# ADC108S022_PINOUT.net
KiCad netlist of a schematic drawn in Altium Designer
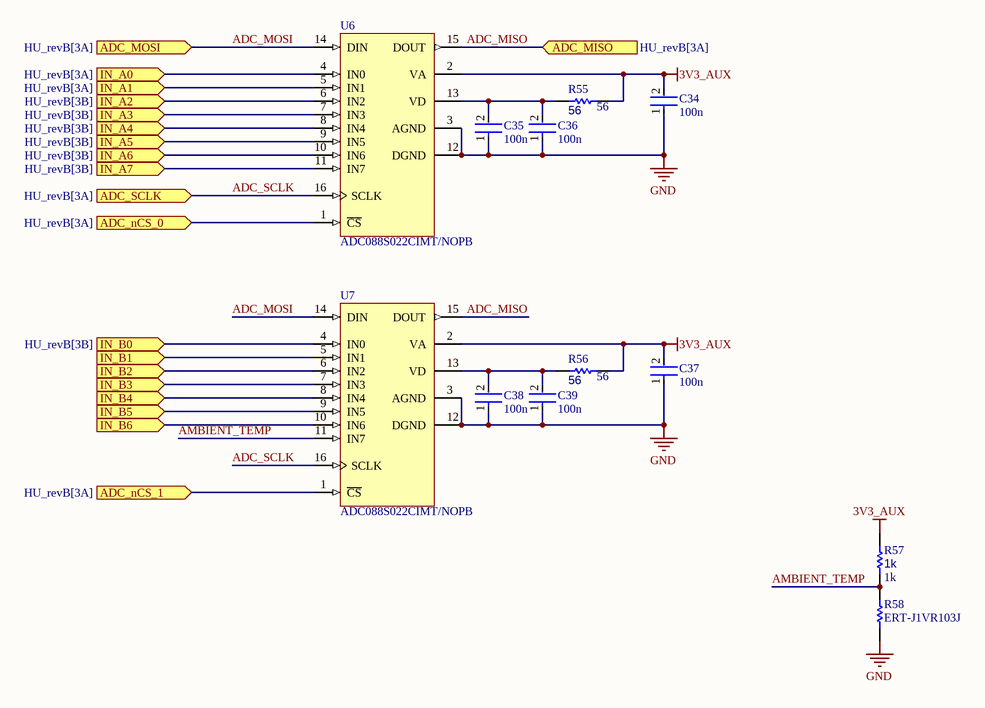
[diagram p0: ADC108S022_PINOUT.SchDoc]

(export (version "E")
  (design (tool "Eeschema 10.0.6"))
  (components
    (comp (ref "C34")
      (value "100n")
      (footprint "FP-0402-L_1_0_0_05-W_0_5-IPC_A")
      (description "LARGE PADS, 0402 CAP, CHANGE COMMENT TO MATCH REAL P/N")
      (libsource (lib "Space Concordia") (part "b4654b650e69147ec39a6b967a45e02"))
    )
    (comp (ref "C35")
      (value "100n")
      (footprint "FP-0402-L_1_0_0_05-W_0_5-IPC_A")
      (description "LARGE PADS, 0402 CAP, CHANGE COMMENT TO MATCH REAL P/N")
      (libsource (lib "Space Concordia") (part "b4654b650e69147ec39a6b967a45e02"))
    )
    (comp (ref "C36")
      (value "100n")
      (footprint "FP-0402-L_1_0_0_05-W_0_5-IPC_A")
      (description "LARGE PADS, 0402 CAP, CHANGE COMMENT TO MATCH REAL P/N")
      (libsource (lib "Space Concordia") (part "b4654b650e69147ec39a6b967a45e02"))
    )
    (comp (ref "C37")
      (value "100n")
      (footprint "FP-0402-L_1_0_0_05-W_0_5-IPC_A")
      (description "LARGE PADS, 0402 CAP, CHANGE COMMENT TO MATCH REAL P/N")
      (libsource (lib "Space Concordia") (part "b4654b650e69147ec39a6b967a45e02"))
    )
    (comp (ref "C38")
      (value "100n")
      (footprint "FP-0402-L_1_0_0_05-W_0_5-IPC_A")
      (description "LARGE PADS, 0402 CAP, CHANGE COMMENT TO MATCH REAL P/N")
      (libsource (lib "Space Concordia") (part "b4654b650e69147ec39a6b967a45e02"))
    )
    (comp (ref "C39")
      (value "100n")
      (footprint "FP-0402-L_1_0_0_05-W_0_5-IPC_A")
      (description "LARGE PADS, 0402 CAP, CHANGE COMMENT TO MATCH REAL P/N")
      (libsource (lib "Space Concordia") (part "b4654b650e69147ec39a6b967a45e02"))
    )
    (comp (ref "R55")
      (value "56")
      (footprint "R0603B")
      (description "Resistor")
      (fields (field (name "ALTIUM_VALUE") "56"))
      (libsource (lib "Space Concordia") (part "Resistor"))
    )
    (comp (ref "R56")
      (value "56")
      (footprint "R0603B")
      (description "Resistor")
      (fields (field (name "ALTIUM_VALUE") "56"))
      (libsource (lib "Space Concordia") (part "Resistor"))
    )
    (comp (ref "R57")
      (value "1k")
      (footprint "R0603B")
      (description "Resistor")
      (fields (field (name "ALTIUM_VALUE") "1k"))
      (libsource (lib "Space Concordia") (part "Resistor"))
    )
    (comp (ref "R58")
      (value "ERT-J1VR103J")
      (footprint "RESC1608X90X30ML15T20")
      (fields (field (name "MANUFACTURER") "Panasonic"))
      (libsource (lib "Altium Content Vault") (part "RES"))
    )
    (comp (ref "U6")
      (value "ADC088S022CIMT/NOPB")
      (footprint "MTC16_L")
      (description "8-Channel, 50 kSPS to 200 kSPS, 8-Bit A/D Converter, 16-pin TSSOP, Pb-Free")
      (fields (field (name "MANUFACTURER") "National Semiconductor"))
      (libsource (lib "Altium Content Vault") (part "CON-ADC-ADC108S052CIMT"))
    )
    (comp (ref "U7")
      (value "ADC088S022CIMT/NOPB")
      (footprint "MTC16_L")
      (description "8-Channel, 50 kSPS to 200 kSPS, 8-Bit A/D Converter, 16-pin TSSOP, Pb-Free")
      (fields (field (name "MANUFACTURER") "National Semiconductor"))
      (libsource (lib "Altium Content Vault") (part "CON-ADC-ADC108S052CIMT"))
    )
  )
  (nets
    (net (code "1") (name "/ADC_MISO") (class "Default")
      (node (ref "U6") (pin "15") (pinfunction "DOUT_15") (pintype "output"))
      (node (ref "U7") (pin "15") (pinfunction "DOUT_15") (pintype "output"))
    )
    (net (code "2") (name "/ADC_MOSI") (class "Default")
      (node (ref "U6") (pin "14") (pinfunction "DIN_14") (pintype "input"))
      (node (ref "U7") (pin "14") (pinfunction "DIN_14") (pintype "input"))
    )
    (net (code "3") (name "/ADC_SCLK") (class "Default")
      (node (ref "U6") (pin "16") (pinfunction "SCLK_16") (pintype "input"))
      (node (ref "U7") (pin "16") (pinfunction "SCLK_16") (pintype "input"))
    )
    (net (code "4") (name "/ADC_nCS_0") (class "Default")
      (node (ref "U6") (pin "1") (pinfunction "~{CS}_1") (pintype "input"))
    )
    (net (code "5") (name "/ADC_nCS_1") (class "Default")
      (node (ref "U7") (pin "1") (pinfunction "~{CS}_1") (pintype "input"))
    )
    (net (code "6") (name "/AMBIENT_TEMP") (class "Default")
      (node (ref "R57") (pin "2") (pinfunction "2_2") (pintype "passive"))
      (node (ref "R58") (pin "2") (pinfunction "2_2") (pintype "passive"))
      (node (ref "U7") (pin "11") (pinfunction "IN7_11") (pintype "input"))
    )
    (net (code "7") (name "/IN_A0") (class "Default")
      (node (ref "U6") (pin "4") (pinfunction "IN0_4") (pintype "input"))
    )
    (net (code "8") (name "/IN_A1") (class "Default")
      (node (ref "U6") (pin "5") (pinfunction "IN1_5") (pintype "input"))
    )
    (net (code "9") (name "/IN_A2") (class "Default")
      (node (ref "U6") (pin "6") (pinfunction "IN2_6") (pintype "input"))
    )
    (net (code "10") (name "/IN_A3") (class "Default")
      (node (ref "U6") (pin "7") (pinfunction "IN3_7") (pintype "input"))
    )
    (net (code "11") (name "/IN_A4") (class "Default")
      (node (ref "U6") (pin "8") (pinfunction "IN4_8") (pintype "input"))
    )
    (net (code "12") (name "/IN_A5") (class "Default")
      (node (ref "U6") (pin "9") (pinfunction "IN5_9") (pintype "input"))
    )
    (net (code "13") (name "/IN_A6") (class "Default")
      (node (ref "U6") (pin "10") (pinfunction "IN6_10") (pintype "input"))
    )
    (net (code "14") (name "/IN_A7") (class "Default")
      (node (ref "U6") (pin "11") (pinfunction "IN7_11") (pintype "input"))
    )
    (net (code "15") (name "/IN_B0") (class "Default")
      (node (ref "U7") (pin "4") (pinfunction "IN0_4") (pintype "input"))
    )
    (net (code "16") (name "/IN_B1") (class "Default")
      (node (ref "U7") (pin "5") (pinfunction "IN1_5") (pintype "input"))
    )
    (net (code "17") (name "/IN_B2") (class "Default")
      (node (ref "U7") (pin "6") (pinfunction "IN2_6") (pintype "input"))
    )
    (net (code "18") (name "/IN_B3") (class "Default")
      (node (ref "U7") (pin "7") (pinfunction "IN3_7") (pintype "input"))
    )
    (net (code "19") (name "/IN_B4") (class "Default")
      (node (ref "U7") (pin "8") (pinfunction "IN4_8") (pintype "input"))
    )
    (net (code "20") (name "/IN_B5") (class "Default")
      (node (ref "U7") (pin "9") (pinfunction "IN5_9") (pintype "input"))
    )
    (net (code "21") (name "/IN_B6") (class "Default")
      (node (ref "U7") (pin "10") (pinfunction "IN6_10") (pintype "input"))
    )
    (net (code "22") (name "3V3_AUX") (class "Default")
      (node (ref "C34") (pin "2") (pinfunction "2_2") (pintype "passive"))
      (node (ref "C37") (pin "2") (pinfunction "2_2") (pintype "passive"))
      (node (ref "R55") (pin "1") (pinfunction "1_1") (pintype "passive"))
      (node (ref "R56") (pin "1") (pinfunction "1_1") (pintype "passive"))
      (node (ref "R57") (pin "1") (pinfunction "1_1") (pintype "passive"))
      (node (ref "U6") (pin "2") (pinfunction "VA_2") (pintype "power_in"))
      (node (ref "U7") (pin "2") (pinfunction "VA_2") (pintype "power_in"))
    )
    (net (code "23") (name "GND") (class "Default")
      (node (ref "C34") (pin "1") (pinfunction "1_1") (pintype "passive"))
      (node (ref "C35") (pin "1") (pinfunction "1_1") (pintype "passive"))
      (node (ref "C36") (pin "1") (pinfunction "1_1") (pintype "passive"))
      (node (ref "C37") (pin "1") (pinfunction "1_1") (pintype "passive"))
      (node (ref "C38") (pin "1") (pinfunction "1_1") (pintype "passive"))
      (node (ref "C39") (pin "1") (pinfunction "1_1") (pintype "passive"))
      (node (ref "R58") (pin "1") (pinfunction "1_1") (pintype "passive"))
      (node (ref "U6") (pin "12") (pinfunction "DGND_12") (pintype "power_in"))
      (node (ref "U6") (pin "3") (pinfunction "AGND_3") (pintype "power_in"))
      (node (ref "U7") (pin "12") (pinfunction "DGND_12") (pintype "power_in"))
      (node (ref "U7") (pin "3") (pinfunction "AGND_3") (pintype "power_in"))
    )
    (net (code "24") (name "Net-(U6-VD)") (class "Default")
      (node (ref "C35") (pin "2") (pinfunction "2_2") (pintype "passive"))
      (node (ref "C36") (pin "2") (pinfunction "2_2") (pintype "passive"))
      (node (ref "R55") (pin "2") (pinfunction "2_2") (pintype "passive"))
      (node (ref "U6") (pin "13") (pinfunction "VD_13") (pintype "power_in"))
    )
    (net (code "25") (name "Net-(U7-VD)") (class "Default")
      (node (ref "C38") (pin "2") (pinfunction "2_2") (pintype "passive"))
      (node (ref "C39") (pin "2") (pinfunction "2_2") (pintype "passive"))
      (node (ref "R56") (pin "2") (pinfunction "2_2") (pintype "passive"))
      (node (ref "U7") (pin "13") (pinfunction "VD_13") (pintype "power_in"))
    )
  )
)
